# SENSORS.net
KiCad netlist of a schematic drawn in Altium Designer
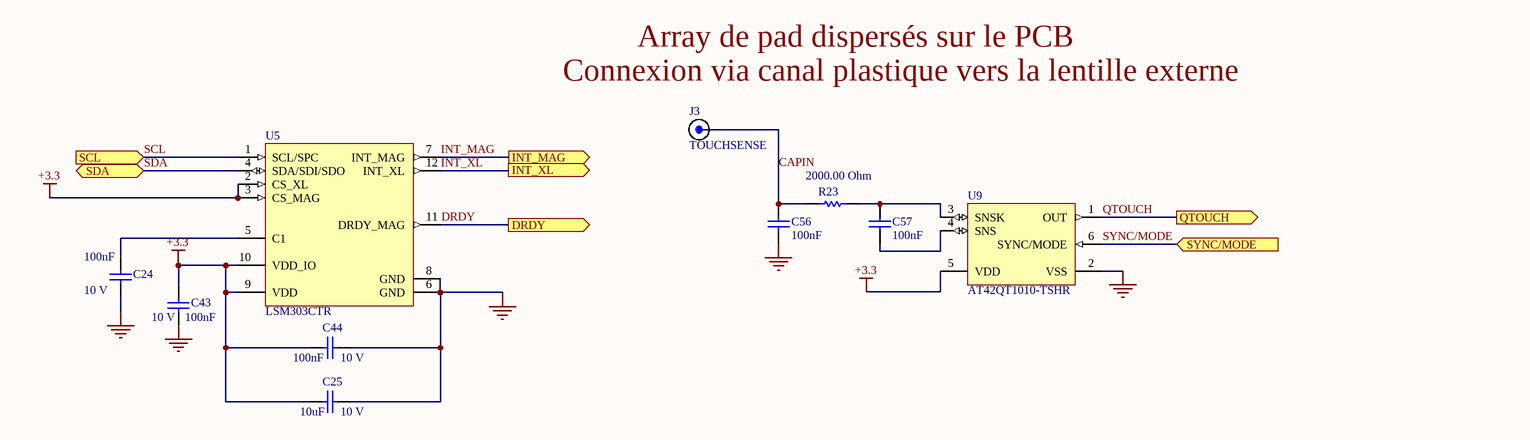
[diagram p0: SENSORS.SchDoc]

(export (version "E")
  (design (tool "Eeschema 10.0.6"))
  (components
    (comp (ref "C24")
      (value "100nF")
      (footprint "CAPC0402(1005)60_L")
      (description "CAP 100nF 10V Â±5% 0402 (1005 Metric) Thickness 0.6mm SMD")
      (fields
        (field (name "TOLERANCE") "Â±5%")
        (field (name "RATED VOLTAGE") "10 V")
        (field (name "Comment") "CAP 100nF 10V 0402(1005)")
      )
      (libsource (lib "Altium Content Vault") (part "CMP-1034-02064-1"))
    )
    (comp (ref "C25")
      (value "10uF")
      (footprint "CAPC0603(1608)100_N")
      (description "CAP 10uF 10V Â±10% 0603 (1608 Metric) Thickness 1mm SMD")
      (fields
        (field (name "TOLERANCE") "Â±10%")
        (field (name "RATED VOLTAGE") "10 V")
        (field (name "Comment") "CAP 10uF 10V 0603(1608)")
      )
      (libsource (lib "Altium Content Vault") (part "CMP-1035-02799-1"))
    )
    (comp (ref "C43")
      (value "100nF")
      (footprint "CAPC0402(1005)60_L")
      (description "CAP 100nF 10V Â±5% 0402 (1005 Metric) Thickness 0.6mm SMD")
      (fields
        (field (name "TOLERANCE") "Â±5%")
        (field (name "RATED VOLTAGE") "10 V")
        (field (name "Comment") "CAP 100nF 10V 0402(1005)")
      )
      (libsource (lib "Altium Content Vault") (part "CMP-1034-02064-1"))
    )
    (comp (ref "C44")
      (value "100nF")
      (footprint "CAPC0402(1005)60_L")
      (description "CAP 100nF 10V Â±5% 0402 (1005 Metric) Thickness 0.6mm SMD")
      (fields
        (field (name "TOLERANCE") "Â±5%")
        (field (name "RATED VOLTAGE") "10 V")
        (field (name "Comment") "CAP 100nF 10V 0402(1005)")
      )
      (libsource (lib "Altium Content Vault") (part "CMP-1034-02064-1"))
    )
    (comp (ref "C56")
      (value "100nF")
      (footprint "CAPC0402(1005)60_L")
      (description "CAP 100nF 10V Â±5% 0402 (1005 Metric) Thickness 0.6mm SMD")
      (fields (field (name "TOLERANCE") "Â±5%") (field (name "Comment") "CAP 100nF 10V 0402(1005)"))
      (libsource (lib "Altium Content Vault") (part "CMP-1034-02064-1"))
    )
    (comp (ref "C57")
      (value "100nF")
      (footprint "CAPC0402(1005)60_L")
      (description "CAP 100nF 10V Â±5% 0402 (1005 Metric) Thickness 0.6mm SMD")
      (fields (field (name "TOLERANCE") "Â±5%") (field (name "Comment") "CAP 100nF 10V 0402(1005)"))
      (libsource (lib "Altium Content Vault") (part "CMP-1034-02064-1"))
    )
    (comp (ref "J3")
      (value "TOUCHSENSE")
      (footprint "TOUCHSENSE")
      (description "Touch Sensor pad connection")
      (libsource (lib "SmartHalo") (part "TOUCHSENSE"))
    )
    (comp (ref "R23")
      (value "2000.00 Ohm")
      (footprint "RESC0603(1608)_N")
      (description "2K 0.1W 5% 0603 (1608 Metric)  SMD")
      (fields (field (name "TOLERANCE") "5 %") (field (name "POWER") "0.1 W"))
      (libsource (lib "Altium Content Vault") (part "CMP-1012-00081-1"))
    )
    (comp (ref "U5")
      (value "LSM303CTR")
      (footprint "SmartHalo:LGA12-2X2X1_N")
      (description "3D ACCELEROMETER/MAGNETOMETER")
      (libsource (lib "SmartHalo") (part "SEN-MOT-LSM303CTR-12"))
    )
    (comp (ref "U9")
      (value "AT42QT1010-TSHR")
      (footprint "6ST1_M")
      (description "One-channel Touch Sensor IC with Reset Timer, -40Â° to +85Â° C, 6-pin SOT23")
      (libsource (lib "Altium Content Vault") (part "IN-TSC-AT42QT1010-6"))
    )
  )
  (nets
    (net (code "1") (name "+3.3") (class "Default")
      (node (ref "C25") (pin "2") (pinfunction "2_2") (pintype "passive"))
      (node (ref "C43") (pin "1") (pinfunction "1_1") (pintype "passive"))
      (node (ref "C44") (pin "2") (pinfunction "2_2") (pintype "passive"))
      (node (ref "U5") (pin "10") (pinfunction "VDD_IO_10") (pintype "power_in"))
      (node (ref "U5") (pin "2") (pinfunction "CS_XL_2") (pintype "input"))
      (node (ref "U5") (pin "3") (pinfunction "CS_MAG_3") (pintype "input"))
      (node (ref "U5") (pin "9") (pinfunction "VDD_9") (pintype "power_in"))
      (node (ref "U9") (pin "5") (pinfunction "VDD_5") (pintype "power_in"))
    )
    (net (code "2") (name "/CAPIN") (class "Default")
      (node (ref "C56") (pin "2") (pinfunction "2_2") (pintype "passive"))
      (node (ref "J3") (pin "1") (pinfunction "1_1") (pintype "passive"))
      (node (ref "R23") (pin "2") (pinfunction "2_2") (pintype "passive"))
    )
    (net (code "3") (name "/DRDY") (class "Default")
      (node (ref "U5") (pin "11") (pinfunction "DRDY_MAG_11") (pintype "output"))
    )
    (net (code "4") (name "/INT_MAG") (class "Default")
      (node (ref "U5") (pin "7") (pinfunction "INT_MAG_7") (pintype "output"))
    )
    (net (code "5") (name "/INT_XL") (class "Default")
      (node (ref "U5") (pin "12") (pinfunction "INT_XL_12") (pintype "output"))
    )
    (net (code "6") (name "/QTOUCH") (class "Default")
      (node (ref "U9") (pin "1") (pinfunction "OUT_1") (pintype "output"))
    )
    (net (code "7") (name "/SCL") (class "Default")
      (node (ref "U5") (pin "1") (pinfunction "SCL/SPC_1") (pintype "input"))
    )
    (net (code "8") (name "/SDA") (class "Default")
      (node (ref "U5") (pin "4") (pinfunction "SDA/SDI/SDO_4") (pintype "bidirectional"))
    )
    (net (code "9") (name "/SYNC{slash}MODE") (class "Default")
      (node (ref "U9") (pin "6") (pinfunction "SYNC/MODE_6") (pintype "input"))
    )
    (net (code "10") (name "GND") (class "Default")
      (node (ref "C24") (pin "2") (pinfunction "2_2") (pintype "passive"))
      (node (ref "C25") (pin "1") (pinfunction "1_1") (pintype "passive"))
      (node (ref "C43") (pin "2") (pinfunction "2_2") (pintype "passive"))
      (node (ref "C44") (pin "1") (pinfunction "1_1") (pintype "passive"))
      (node (ref "C56") (pin "1") (pinfunction "1_1") (pintype "passive"))
      (node (ref "U5") (pin "6") (pinfunction "GND_6") (pintype "power_in"))
      (node (ref "U5") (pin "8") (pinfunction "GND_8") (pintype "power_in"))
      (node (ref "U9") (pin "2") (pinfunction "VSS_2") (pintype "power_in"))
    )
    (net (code "11") (name "Net-(U5-C1)") (class "Default")
      (node (ref "C24") (pin "1") (pinfunction "1_1") (pintype "passive"))
      (node (ref "U5") (pin "5") (pinfunction "C1_5") (pintype "passive"))
    )
    (net (code "12") (name "Net-(U9-SNS)") (class "Default")
      (node (ref "C57") (pin "1") (pinfunction "1_1") (pintype "passive"))
      (node (ref "U9") (pin "4") (pinfunction "SNS_4") (pintype "bidirectional"))
    )
    (net (code "13") (name "Net-(U9-SNSK)") (class "Default")
      (node (ref "C57") (pin "2") (pinfunction "2_2") (pintype "passive"))
      (node (ref "R23") (pin "1") (pinfunction "1_1") (pintype "passive"))
      (node (ref "U9") (pin "3") (pinfunction "SNSK_3") (pintype "bidirectional"))
    )
  )
)
